# EPS_MPPT_X_Boost-Converter.net
KiCad netlist of a schematic drawn in Altium Designer
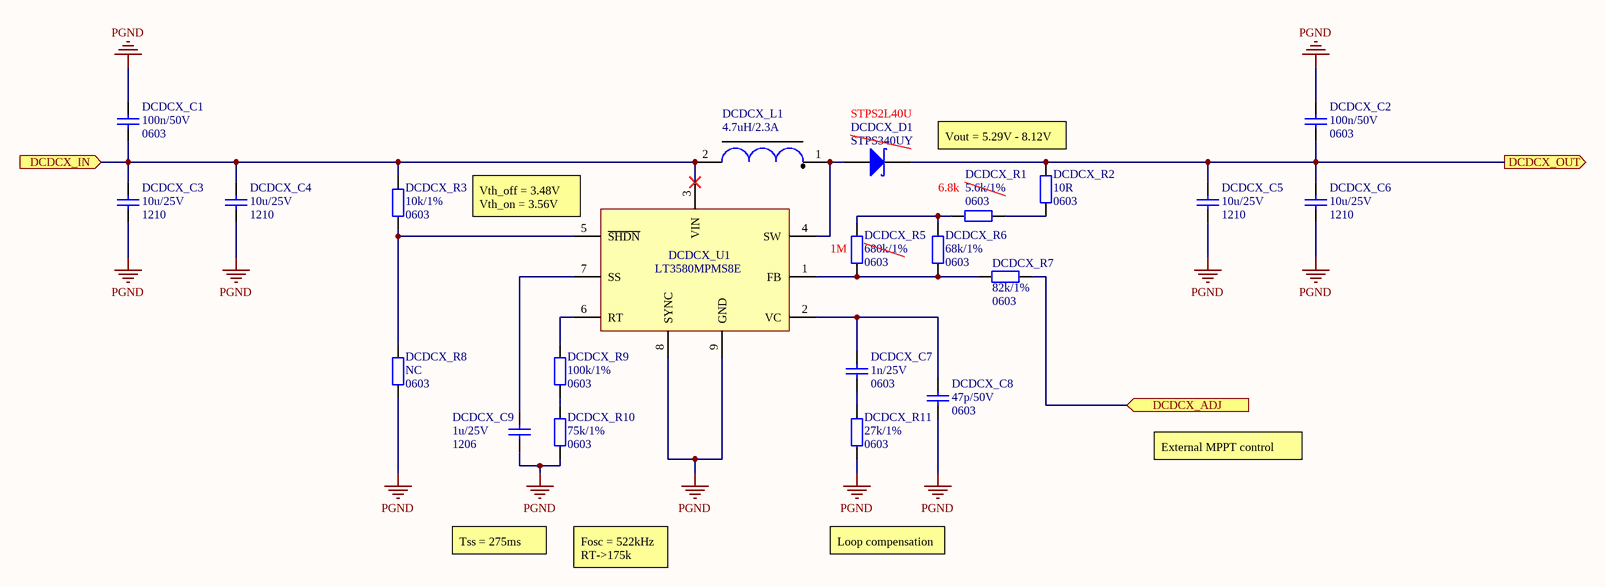
[diagram p0: EPS_MPPT_X_Boost-Converter.SchDoc]

(export (version "E")
  (design (tool "Eeschema 10.0.6"))
  (components
    (comp (ref "DCDCX_C1")
      (value "100n/50V")
      (footprint "SMD_Capacitor_0603")
      (description "Ceramic Cap Kemet COTS 100n/50V X7R 0603")
      (fields
        (field (name "MANUFACTURER") "Kemet")
        (field (name "MANUFACTURERPARTNUMBER") "C0603T104K5RALTU")
        (field (name "PACKAGE") "0603")
      )
      (libsource (lib "capacitors") (part "Cer_C0603T104K5RALTU"))
    )
    (comp (ref "DCDCX_C2")
      (value "100n/50V")
      (footprint "SMD_Capacitor_0603")
      (description "Ceramic Cap Kemet COTS 100n/50V X7R 0603")
      (fields
        (field (name "MANUFACTURER") "Kemet")
        (field (name "MANUFACTURERPARTNUMBER") "C0603T104K5RALTU")
        (field (name "PACKAGE") "0603")
      )
      (libsource (lib "capacitors") (part "Cer_C0603T104K5RALTU"))
    )
    (comp (ref "DCDCX_C3")
      (value "10u/25V")
      (footprint "SMD_Capacitor_1210")
      (description "Ceramic Cap Murata Automotive 10u/25V X7R 1210")
      (fields
        (field (name "MANUFACTURER") "Murata")
        (field (name "MANUFACTURERPARTNUMBER") "GCJ32ER71E106KA12L")
        (field (name "PACKAGE") "1210")
      )
      (libsource (lib "capacitors") (part "Cer_GCJ32ER71E106KA12L"))
    )
    (comp (ref "DCDCX_C4")
      (value "10u/25V")
      (footprint "SMD_Capacitor_1210")
      (description "Ceramic Cap Murata Automotive 10u/25V X7R 1210")
      (fields
        (field (name "MANUFACTURER") "Murata")
        (field (name "MANUFACTURERPARTNUMBER") "GCJ32ER71E106KA12L")
        (field (name "PACKAGE") "1210")
      )
      (libsource (lib "capacitors") (part "Cer_GCJ32ER71E106KA12L"))
    )
    (comp (ref "DCDCX_C5")
      (value "10u/25V")
      (footprint "SMD_Capacitor_1210")
      (description "Ceramic Cap Murata Automotive 10u/25V X7R 1210")
      (fields
        (field (name "MANUFACTURER") "Murata")
        (field (name "MANUFACTURERPARTNUMBER") "GCJ32ER71E106KA12L")
        (field (name "PACKAGE") "1210")
      )
      (libsource (lib "capacitors") (part "Cer_GCJ32ER71E106KA12L"))
    )
    (comp (ref "DCDCX_C6")
      (value "10u/25V")
      (footprint "SMD_Capacitor_1210")
      (description "Ceramic Cap Murata Automotive 10u/25V X7R 1210")
      (fields
        (field (name "MANUFACTURER") "Murata")
        (field (name "MANUFACTURERPARTNUMBER") "GCJ32ER71E106KA12L")
        (field (name "PACKAGE") "1210")
      )
      (libsource (lib "capacitors") (part "Cer_GCJ32ER71E106KA12L"))
    )
    (comp (ref "DCDCX_C7")
      (value "1n/25V")
      (footprint "SMD_Capacitor_0603")
      (description "Cap")
      (fields (field (name "PACKAGE") "0603"))
      (libsource (lib "capacitors") (part "Cap"))
    )
    (comp (ref "DCDCX_C8")
      (value "47p/50V")
      (footprint "SMD_Capacitor_0603")
      (description "Cap")
      (fields (field (name "PACKAGE") "0603"))
      (libsource (lib "capacitors") (part "Cap"))
    )
    (comp (ref "DCDCX_C9")
      (value "1u/25V")
      (footprint "SMD_Capacitor_1206")
      (description "Ceramic Cap Kemet COTS 1u/25V X7R 1206")
      (fields
        (field (name "MANUFACTURERPARTNUMBER") "C1206T105K3RALTU")
        (field (name "MANUFACTURER") "Kemet")
        (field (name "PACKAGE") "1206")
      )
      (libsource (lib "capacitors") (part "Cer_C1206T105K3RALTU"))
    )
    (comp (ref "DCDCX_D1")
      (value "STPS340UY")
      (footprint "DO-214AA")
      (description "3A/40V Power Schottky Rectifier.")
      (fields (field (name "MANUFACTURER") "STMicroelectronics"))
      (libsource (lib "diodes") (part "STPS340x"))
    )
    (comp (ref "DCDCX_L1")
      (value "4.7uH/2.3A")
      (footprint "Coilcraft_MSS6132")
      (description "Coilcraft MSS6132 Inductor, L=4.7uH, Irise20deg=2.3A, ESR=43mR, SRF=65MHz.")
      (fields
        (field (name "MANUFACTURER") "Coilcraft")
        (field (name "MANUFACTURERPARTNUMBER") "MSS6132-472MLx")
      )
      (libsource (lib "inductors") (part "MSS6132-472MLx"))
    )
    (comp (ref "DCDCX_R1")
      (value "5.6k/1%")
      (footprint "SMD_Resistor_0603")
      (fields (field (name "PACKAGE") "0603"))
      (libsource (lib "") (part "Res_1"))
    )
    (comp (ref "DCDCX_R2")
      (value "10R")
      (footprint "SMD_Resistor_0603")
      (fields (field (name "PACKAGE") "0603"))
      (libsource (lib "") (part "Res_2"))
    )
    (comp (ref "DCDCX_R3")
      (value "10k/1%")
      (footprint "SMD_Resistor_0603")
      (fields (field (name "PACKAGE") "0603"))
      (libsource (lib "resistors") (part "Res"))
    )
    (comp (ref "DCDCX_R5")
      (value "680k/1%")
      (footprint "SMD_Resistor_0603")
      (fields (field (name "PACKAGE") "0603"))
      (libsource (lib "resistors") (part "Res"))
    )
    (comp (ref "DCDCX_R6")
      (value "68k/1%")
      (footprint "SMD_Resistor_0603")
      (fields (field (name "PACKAGE") "0603"))
      (libsource (lib "resistors") (part "Res"))
    )
    (comp (ref "DCDCX_R7")
      (value "82k/1%")
      (footprint "SMD_Resistor_0603")
      (fields (field (name "PACKAGE") "0603"))
      (libsource (lib "") (part "Res_1"))
    )
    (comp (ref "DCDCX_R8")
      (value "NC")
      (footprint "SMD_Resistor_0603")
      (fields (field (name "PACKAGE") "0603"))
      (libsource (lib "resistors") (part "Res"))
    )
    (comp (ref "DCDCX_R9")
      (value "100k/1%")
      (footprint "SMD_Resistor_0603")
      (fields (field (name "PACKAGE") "0603"))
      (libsource (lib "resistors") (part "Res"))
    )
    (comp (ref "DCDCX_R10")
      (value "75k/1%")
      (footprint "SMD_Resistor_0603")
      (fields (field (name "PACKAGE") "0603"))
      (libsource (lib "resistors") (part "Res"))
    )
    (comp (ref "DCDCX_R11")
      (value "27k/1%")
      (footprint "SMD_Resistor_0603")
      (fields (field (name "PACKAGE") "0603"))
      (libsource (lib "resistors") (part "Res"))
    )
    (comp (ref "DCDCX_U1")
      (value "~")
      (footprint "LT-MS8E-8-1880X1680TP_N")
      (description "Boost Conv 2A, Soft-Start, Synchro")
      (fields
        (field (name "MANUFACTURER") "Linear Technology")
        (field (name "MANUFACTURERPARTNUMBER") "LT3580MPMS8E")
      )
      (libsource (lib "microcircuits") (part "LT3580MPMS8E"))
    )
  )
  (nets
    (net (code "1") (name "/DCDCX_ADJ") (class "Default")
      (node (ref "DCDCX_R7") (pin "2") (pinfunction "2_2") (pintype "passive"))
    )
    (net (code "2") (name "/DCDCX_IN") (class "Default")
      (node (ref "DCDCX_C1") (pin "2") (pinfunction "2_2") (pintype "passive"))
      (node (ref "DCDCX_C3") (pin "1") (pinfunction "1_1") (pintype "passive"))
      (node (ref "DCDCX_C4") (pin "1") (pinfunction "1_1") (pintype "passive"))
      (node (ref "DCDCX_L1") (pin "2") (pinfunction "2_2") (pintype "passive"))
      (node (ref "DCDCX_R3") (pin "1") (pinfunction "1_1") (pintype "passive"))
      (node (ref "DCDCX_U1") (pin "3") (pinfunction "VIN_3") (pintype "power_in"))
    )
    (net (code "3") (name "/DCDCX_OUT") (class "Default")
      (node (ref "DCDCX_C2") (pin "2") (pinfunction "2_2") (pintype "passive"))
      (node (ref "DCDCX_C5") (pin "1") (pinfunction "1_1") (pintype "passive"))
      (node (ref "DCDCX_C6") (pin "1") (pinfunction "1_1") (pintype "passive"))
      (node (ref "DCDCX_D1") (pin "K") (pinfunction "K_K") (pintype "passive"))
      (node (ref "DCDCX_R2") (pin "2") (pinfunction "2_2") (pintype "passive"))
    )
    (net (code "4") (name "Net-(DCDCX_C7-Pad2)") (class "Default")
      (node (ref "DCDCX_C7") (pin "2") (pinfunction "2_2") (pintype "passive"))
      (node (ref "DCDCX_R11") (pin "1") (pinfunction "1_1") (pintype "passive"))
    )
    (net (code "5") (name "Net-(DCDCX_R1-Pad1)") (class "Default")
      (node (ref "DCDCX_R1") (pin "1") (pinfunction "1_1") (pintype "passive"))
      (node (ref "DCDCX_R5") (pin "1") (pinfunction "1_1") (pintype "passive"))
      (node (ref "DCDCX_R6") (pin "1") (pinfunction "1_1") (pintype "passive"))
    )
    (net (code "6") (name "Net-(DCDCX_R1-Pad2)") (class "Default")
      (node (ref "DCDCX_R1") (pin "2") (pinfunction "2_2") (pintype "passive"))
      (node (ref "DCDCX_R2") (pin "1") (pinfunction "1_1") (pintype "passive"))
    )
    (net (code "7") (name "Net-(DCDCX_R10-Pad1)") (class "Default")
      (node (ref "DCDCX_R10") (pin "1") (pinfunction "1_1") (pintype "passive"))
      (node (ref "DCDCX_R9") (pin "2") (pinfunction "2_2") (pintype "passive"))
    )
    (net (code "8") (name "Net-(DCDCX_U1-FB)") (class "Default")
      (node (ref "DCDCX_R5") (pin "2") (pinfunction "2_2") (pintype "passive"))
      (node (ref "DCDCX_R6") (pin "2") (pinfunction "2_2") (pintype "passive"))
      (node (ref "DCDCX_R7") (pin "1") (pinfunction "1_1") (pintype "passive"))
      (node (ref "DCDCX_U1") (pin "1") (pinfunction "FB_1") (pintype "passive"))
    )
    (net (code "9") (name "Net-(DCDCX_U1-RT)") (class "Default")
      (node (ref "DCDCX_R9") (pin "1") (pinfunction "1_1") (pintype "passive"))
      (node (ref "DCDCX_U1") (pin "6") (pinfunction "RT_6") (pintype "passive"))
    )
    (net (code "10") (name "Net-(DCDCX_U1-SS)") (class "Default")
      (node (ref "DCDCX_C9") (pin "1") (pinfunction "1_1") (pintype "passive"))
      (node (ref "DCDCX_U1") (pin "7") (pinfunction "SS_7") (pintype "passive"))
    )
    (net (code "11") (name "Net-(DCDCX_U1-SW)") (class "Default")
      (node (ref "DCDCX_D1") (pin "A") (pinfunction "A_A") (pintype "passive"))
      (node (ref "DCDCX_L1") (pin "1") (pinfunction "1_1") (pintype "passive"))
      (node (ref "DCDCX_U1") (pin "4") (pinfunction "SW_4") (pintype "passive"))
    )
    (net (code "12") (name "Net-(DCDCX_U1-VC)") (class "Default")
      (node (ref "DCDCX_C7") (pin "1") (pinfunction "1_1") (pintype "passive"))
      (node (ref "DCDCX_C8") (pin "1") (pinfunction "1_1") (pintype "passive"))
      (node (ref "DCDCX_U1") (pin "2") (pinfunction "VC_2") (pintype "passive"))
    )
    (net (code "13") (name "Net-(DCDCX_U1-~{SHDN})") (class "Default")
      (node (ref "DCDCX_R3") (pin "2") (pinfunction "2_2") (pintype "passive"))
      (node (ref "DCDCX_R8") (pin "1") (pinfunction "1_1") (pintype "passive"))
      (node (ref "DCDCX_U1") (pin "5") (pinfunction "~{SHDN}_5") (pintype "passive"))
    )
    (net (code "14") (name "PGND") (class "Default")
      (node (ref "DCDCX_C1") (pin "1") (pinfunction "1_1") (pintype "passive"))
      (node (ref "DCDCX_C2") (pin "1") (pinfunction "1_1") (pintype "passive"))
      (node (ref "DCDCX_C3") (pin "2") (pinfunction "2_2") (pintype "passive"))
      (node (ref "DCDCX_C4") (pin "2") (pinfunction "2_2") (pintype "passive"))
      (node (ref "DCDCX_C5") (pin "2") (pinfunction "2_2") (pintype "passive"))
      (node (ref "DCDCX_C6") (pin "2") (pinfunction "2_2") (pintype "passive"))
      (node (ref "DCDCX_C8") (pin "2") (pinfunction "2_2") (pintype "passive"))
      (node (ref "DCDCX_C9") (pin "2") (pinfunction "2_2") (pintype "passive"))
      (node (ref "DCDCX_R10") (pin "2") (pinfunction "2_2") (pintype "passive"))
      (node (ref "DCDCX_R11") (pin "2") (pinfunction "2_2") (pintype "passive"))
      (node (ref "DCDCX_R8") (pin "2") (pinfunction "2_2") (pintype "passive"))
      (node (ref "DCDCX_U1") (pin "8") (pinfunction "SYNC_8") (pintype "passive"))
      (node (ref "DCDCX_U1") (pin "9") (pinfunction "GND_9") (pintype "passive"))
    )
  )
)
